# integrator_4pole.net
KiCad netlist of a schematic drawn in Altium Designer
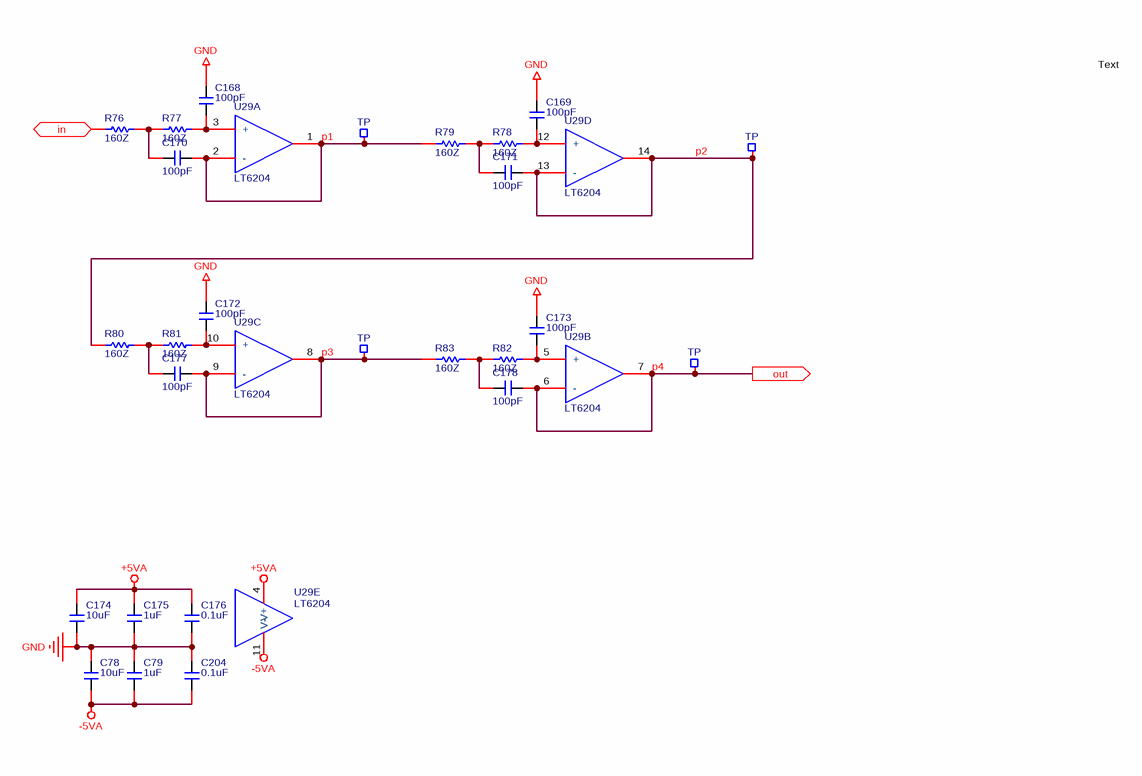
[diagram p0: integrator_4pole.SchDoc]

(export (version "E")
  (design (tool "Eeschema 10.0.6"))
  (components
    (comp (ref "C78")
      (value "10uF")
      (footprint "c1206")
      (description "CAP-CER, 2, 10uF, 10%, 35V, 1206")
      (fields
        (field (name "MANUFACTURER") "Taiyo Yuden")
        (field (name "MANUFACTURER PART NUMBER") "GMK316F106ZL-T")
      )
      (libsource (lib "stdlib") (part "CAP/GMK316F106ZL-T"))
    )
    (comp (ref "C79")
      (value "1uF")
      (footprint "C0603")
      (description "CAP-CER, 2, 1.0uF, 10%, 25V, 0603")
      (fields
        (field (name "MANUFACTURER") "Murata Electronics North America")
        (field (name "MANUFACTURER PART NUMBER") "GRM188R61E105KA12D")
      )
      (libsource (lib "stdlib") (part "Murata/GRM188R61E105KA12D"))
    )
    (comp (ref "C168")
      (value "100pF")
      (footprint "C0603")
      (description "CAP-CER, 0, 100pF, 10%, 50V, 0603")
      (fields
        (field (name "MANUFACTURER") "AVX Corporation")
        (field (name "MANUFACTURER PART NUMBER") "06035A101KAT2A")
      )
      (libsource (lib "stdlib") (part "AVX/06035A101KAT2A"))
    )
    (comp (ref "C169")
      (value "100pF")
      (footprint "C0603")
      (description "CAP-CER, 0, 100pF, 10%, 50V, 0603")
      (fields
        (field (name "MANUFACTURER") "AVX Corporation")
        (field (name "MANUFACTURER PART NUMBER") "06035A101KAT2A")
      )
      (libsource (lib "stdlib") (part "AVX/06035A101KAT2A"))
    )
    (comp (ref "C170")
      (value "100pF")
      (footprint "C0603")
      (description "CAP-CER, 0, 100pF, 10%, 50V, 0603")
      (fields
        (field (name "MANUFACTURER") "AVX Corporation")
        (field (name "MANUFACTURER PART NUMBER") "06035A101KAT2A")
      )
      (libsource (lib "stdlib") (part "AVX/06035A101KAT2A"))
    )
    (comp (ref "C171")
      (value "100pF")
      (footprint "C0603")
      (description "CAP-CER, 0, 100pF, 10%, 50V, 0603")
      (fields
        (field (name "MANUFACTURER") "AVX Corporation")
        (field (name "MANUFACTURER PART NUMBER") "06035A101KAT2A")
      )
      (libsource (lib "stdlib") (part "AVX/06035A101KAT2A"))
    )
    (comp (ref "C172")
      (value "100pF")
      (footprint "C0603")
      (description "CAP-CER, 0, 100pF, 10%, 50V, 0603")
      (fields
        (field (name "MANUFACTURER") "AVX Corporation")
        (field (name "MANUFACTURER PART NUMBER") "06035A101KAT2A")
      )
      (libsource (lib "stdlib") (part "AVX/06035A101KAT2A"))
    )
    (comp (ref "C173")
      (value "100pF")
      (footprint "C0603")
      (description "CAP-CER, 0, 100pF, 10%, 50V, 0603")
      (fields
        (field (name "MANUFACTURER") "AVX Corporation")
        (field (name "MANUFACTURER PART NUMBER") "06035A101KAT2A")
      )
      (libsource (lib "stdlib") (part "AVX/06035A101KAT2A"))
    )
    (comp (ref "C174")
      (value "10uF")
      (footprint "c1206")
      (description "CAP-CER, 2, 10uF, 10%, 35V, 1206")
      (fields
        (field (name "MANUFACTURER") "Taiyo Yuden")
        (field (name "MANUFACTURER PART NUMBER") "GMK316F106ZL-T")
      )
      (libsource (lib "stdlib") (part "CAP/GMK316F106ZL-T"))
    )
    (comp (ref "C175")
      (value "1uF")
      (footprint "C0603")
      (description "CAP-CER, 2, 1.0uF, 10%, 25V, 0603")
      (fields
        (field (name "MANUFACTURER") "Murata Electronics North America")
        (field (name "MANUFACTURER PART NUMBER") "GRM188R61E105KA12D")
      )
      (libsource (lib "stdlib") (part "Murata/GRM188R61E105KA12D"))
    )
    (comp (ref "C176")
      (value "0.1uF")
      (footprint "C0603")
      (description "CAP-CER, 2, 0.1uF, 10%, 50V, 0603, X7R")
      (fields
        (field (name "MANUFACTURER") "AVX Corporation")
        (field (name "MANUFACTURER PART NUMBER") "06035C104KAT2A")
      )
      (libsource (lib "stdlib") (part "CAP/06035C104KAT2A"))
    )
    (comp (ref "C177")
      (value "100pF")
      (footprint "C0603")
      (description "CAP-CER, 0, 100pF, 10%, 50V, 0603")
      (fields
        (field (name "MANUFACTURER") "AVX Corporation")
        (field (name "MANUFACTURER PART NUMBER") "06035A101KAT2A")
      )
      (libsource (lib "stdlib") (part "AVX/06035A101KAT2A"))
    )
    (comp (ref "C178")
      (value "100pF")
      (footprint "C0603")
      (description "CAP-CER, 0, 100pF, 10%, 50V, 0603")
      (fields
        (field (name "MANUFACTURER") "AVX Corporation")
        (field (name "MANUFACTURER PART NUMBER") "06035A101KAT2A")
      )
      (libsource (lib "stdlib") (part "AVX/06035A101KAT2A"))
    )
    (comp (ref "C204")
      (value "0.1uF")
      (footprint "C0603")
      (description "CAP-CER, 2, 0.1uF, 10%, 50V, 0603, X7R")
      (fields
        (field (name "MANUFACTURER") "AVX Corporation")
        (field (name "MANUFACTURER PART NUMBER") "06035C104KAT2A")
      )
      (libsource (lib "stdlib") (part "CAP/06035C104KAT2A"))
    )
    (comp (ref "R76")
      (value "160Z")
      (footprint "R0603")
      (description "RES0, SMD,  160Z, 1.0%, 1/10W, 0603")
      (fields
        (field (name "MANUFACTURER") "Vishay Dale")
        (field (name "MANUFACTURER PART NUMBER") "CRCW0603160RFKEA")
      )
      (libsource (lib "stdlib") (part "CRCW0603160RFKEA"))
    )
    (comp (ref "R77")
      (value "160Z")
      (footprint "R0603")
      (description "RES0, SMD,  160Z, 1.0%, 1/10W, 0603")
      (fields
        (field (name "MANUFACTURER") "Vishay Dale")
        (field (name "MANUFACTURER PART NUMBER") "CRCW0603160RFKEA")
      )
      (libsource (lib "stdlib") (part "CRCW0603160RFKEA"))
    )
    (comp (ref "R78")
      (value "160Z")
      (footprint "R0603")
      (description "RES0, SMD,  160Z, 1.0%, 1/10W, 0603")
      (fields
        (field (name "MANUFACTURER") "Vishay Dale")
        (field (name "MANUFACTURER PART NUMBER") "CRCW0603160RFKEA")
      )
      (libsource (lib "stdlib") (part "CRCW0603160RFKEA"))
    )
    (comp (ref "R79")
      (value "160Z")
      (footprint "R0603")
      (description "RES0, SMD,  160Z, 1.0%, 1/10W, 0603")
      (fields
        (field (name "MANUFACTURER") "Vishay Dale")
        (field (name "MANUFACTURER PART NUMBER") "CRCW0603160RFKEA")
      )
      (libsource (lib "stdlib") (part "CRCW0603160RFKEA"))
    )
    (comp (ref "R80")
      (value "160Z")
      (footprint "R0603")
      (description "RES0, SMD,  160Z, 1.0%, 1/10W, 0603")
      (fields
        (field (name "MANUFACTURER") "Vishay Dale")
        (field (name "MANUFACTURER PART NUMBER") "CRCW0603160RFKEA")
      )
      (libsource (lib "stdlib") (part "CRCW0603160RFKEA"))
    )
    (comp (ref "R81")
      (value "160Z")
      (footprint "R0603")
      (description "RES0, SMD,  160Z, 1.0%, 1/10W, 0603")
      (fields
        (field (name "MANUFACTURER") "Vishay Dale")
        (field (name "MANUFACTURER PART NUMBER") "CRCW0603160RFKEA")
      )
      (libsource (lib "stdlib") (part "CRCW0603160RFKEA"))
    )
    (comp (ref "R82")
      (value "160Z")
      (footprint "R0603")
      (description "RES0, SMD,  160Z, 1.0%, 1/10W, 0603")
      (fields
        (field (name "MANUFACTURER") "Vishay Dale")
        (field (name "MANUFACTURER PART NUMBER") "CRCW0603160RFKEA")
      )
      (libsource (lib "stdlib") (part "CRCW0603160RFKEA"))
    )
    (comp (ref "R83")
      (value "160Z")
      (footprint "R0603")
      (description "RES0, SMD,  160Z, 1.0%, 1/10W, 0603")
      (fields
        (field (name "MANUFACTURER") "Vishay Dale")
        (field (name "MANUFACTURER PART NUMBER") "CRCW0603160RFKEA")
      )
      (libsource (lib "stdlib") (part "CRCW0603160RFKEA"))
    )
    (comp (ref "TP8")
      (value "TP")
      (footprint "TP_MICRO")
      (description "Test Point, Round, Small")
      (libsource (lib "stdlib") (part "TP_MICRO"))
    )
    (comp (ref "TP33")
      (value "TP")
      (footprint "TP_MICRO")
      (description "Test Point, Round, Small")
      (libsource (lib "stdlib") (part "TP_MICRO"))
    )
    (comp (ref "TP34")
      (value "TP")
      (footprint "TP_MICRO")
      (description "Test Point, Round, Small")
      (libsource (lib "stdlib") (part "TP_MICRO"))
    )
    (comp (ref "TP35")
      (value "TP")
      (footprint "TP_MICRO")
      (description "Test Point, Round, Small")
      (libsource (lib "stdlib") (part "TP_MICRO"))
    )
    (comp (ref "U29")
      (value "LT6204")
      (footprint "SOIC-14")
      (description "OPA, 100MHz, Quad, RRIO, Unity Stable")
      (libsource (lib "stdlib") (part "LT6204 SOIC-14"))
    )
  )
  (nets
    (net (code "1") (name "+5VA") (class "Default")
      (node (ref "C174") (pin "1") (pinfunction "5_1") (pintype "passive"))
      (node (ref "C175") (pin "2") (pinfunction "2_2") (pintype "passive"))
      (node (ref "C176") (pin "2") (pinfunction "2_2") (pintype "passive"))
      (node (ref "U29") (pin "4") (pinfunction "V+_4") (pintype "passive"))
    )
    (net (code "2") (name "-5VA") (class "Default")
      (node (ref "C204") (pin "1") (pinfunction "5_1") (pintype "passive"))
      (node (ref "C78") (pin "2") (pinfunction "2_2") (pintype "passive"))
      (node (ref "C79") (pin "1") (pinfunction "5_1") (pintype "passive"))
      (node (ref "U29") (pin "11") (pinfunction "V-_11") (pintype "passive"))
    )
    (net (code "3") (name "/in") (class "Default")
      (node (ref "R76") (pin "1") (pinfunction "1_1") (pintype "passive"))
    )
    (net (code "4") (name "/p1") (class "Default")
      (node (ref "C170") (pin "2") (pinfunction "2_2") (pintype "passive"))
      (node (ref "R79") (pin "1") (pinfunction "1_1") (pintype "passive"))
      (node (ref "TP8") (pin "1") (pinfunction "1_1") (pintype "passive"))
      (node (ref "U29") (pin "1") (pinfunction "OUT_1") (pintype "passive"))
      (node (ref "U29") (pin "2") (pinfunction "-_2") (pintype "passive"))
    )
    (net (code "5") (name "/p2") (class "Default")
      (node (ref "C171") (pin "2") (pinfunction "2_2") (pintype "passive"))
      (node (ref "R80") (pin "1") (pinfunction "1_1") (pintype "passive"))
      (node (ref "TP33") (pin "1") (pinfunction "1_1") (pintype "passive"))
      (node (ref "U29") (pin "13") (pinfunction "-_13") (pintype "passive"))
      (node (ref "U29") (pin "14") (pinfunction "OUT_14") (pintype "passive"))
    )
    (net (code "6") (name "/p3") (class "Default")
      (node (ref "C177") (pin "2") (pinfunction "2_2") (pintype "passive"))
      (node (ref "R83") (pin "1") (pinfunction "1_1") (pintype "passive"))
      (node (ref "TP34") (pin "1") (pinfunction "1_1") (pintype "passive"))
      (node (ref "U29") (pin "8") (pinfunction "OUT_8") (pintype "passive"))
      (node (ref "U29") (pin "9") (pinfunction "-_9") (pintype "passive"))
    )
    (net (code "7") (name "/p4") (class "Default")
      (node (ref "C178") (pin "2") (pinfunction "2_2") (pintype "passive"))
      (node (ref "TP35") (pin "1") (pinfunction "1_1") (pintype "passive"))
      (node (ref "U29") (pin "6") (pinfunction "-_6") (pintype "passive"))
      (node (ref "U29") (pin "7") (pinfunction "OUT_7") (pintype "passive"))
    )
    (net (code "8") (name "GND") (class "Default")
      (node (ref "C168") (pin "2") (pinfunction "2_2") (pintype "passive"))
      (node (ref "C169") (pin "2") (pinfunction "2_2") (pintype "passive"))
      (node (ref "C172") (pin "2") (pinfunction "2_2") (pintype "passive"))
      (node (ref "C173") (pin "2") (pinfunction "2_2") (pintype "passive"))
      (node (ref "C174") (pin "2") (pinfunction "2_2") (pintype "passive"))
      (node (ref "C175") (pin "1") (pinfunction "5_1") (pintype "passive"))
      (node (ref "C176") (pin "1") (pinfunction "5_1") (pintype "passive"))
      (node (ref "C204") (pin "2") (pinfunction "2_2") (pintype "passive"))
      (node (ref "C78") (pin "1") (pinfunction "5_1") (pintype "passive"))
      (node (ref "C79") (pin "2") (pinfunction "2_2") (pintype "passive"))
    )
    (net (code "9") (name "Net-(C168-5)") (class "Default")
      (node (ref "C168") (pin "1") (pinfunction "5_1") (pintype "passive"))
      (node (ref "R77") (pin "2") (pinfunction "2_2") (pintype "passive"))
      (node (ref "U29") (pin "3") (pinfunction "+_3") (pintype "passive"))
    )
    (net (code "10") (name "Net-(C169-5)") (class "Default")
      (node (ref "C169") (pin "1") (pinfunction "5_1") (pintype "passive"))
      (node (ref "R78") (pin "2") (pinfunction "2_2") (pintype "passive"))
      (node (ref "U29") (pin "12") (pinfunction "+_12") (pintype "passive"))
    )
    (net (code "11") (name "Net-(C170-5)") (class "Default")
      (node (ref "C170") (pin "1") (pinfunction "5_1") (pintype "passive"))
      (node (ref "R76") (pin "2") (pinfunction "2_2") (pintype "passive"))
      (node (ref "R77") (pin "1") (pinfunction "1_1") (pintype "passive"))
    )
    (net (code "12") (name "Net-(C171-5)") (class "Default")
      (node (ref "C171") (pin "1") (pinfunction "5_1") (pintype "passive"))
      (node (ref "R78") (pin "1") (pinfunction "1_1") (pintype "passive"))
      (node (ref "R79") (pin "2") (pinfunction "2_2") (pintype "passive"))
    )
    (net (code "13") (name "Net-(C172-5)") (class "Default")
      (node (ref "C172") (pin "1") (pinfunction "5_1") (pintype "passive"))
      (node (ref "R81") (pin "2") (pinfunction "2_2") (pintype "passive"))
      (node (ref "U29") (pin "10") (pinfunction "+_10") (pintype "passive"))
    )
    (net (code "14") (name "Net-(C173-5)") (class "Default")
      (node (ref "C173") (pin "1") (pinfunction "5_1") (pintype "passive"))
      (node (ref "R82") (pin "2") (pinfunction "2_2") (pintype "passive"))
      (node (ref "U29") (pin "5") (pinfunction "+_5") (pintype "passive"))
    )
    (net (code "15") (name "Net-(C177-5)") (class "Default")
      (node (ref "C177") (pin "1") (pinfunction "5_1") (pintype "passive"))
      (node (ref "R80") (pin "2") (pinfunction "2_2") (pintype "passive"))
      (node (ref "R81") (pin "1") (pinfunction "1_1") (pintype "passive"))
    )
    (net (code "16") (name "Net-(C178-5)") (class "Default")
      (node (ref "C178") (pin "1") (pinfunction "5_1") (pintype "passive"))
      (node (ref "R82") (pin "1") (pinfunction "1_1") (pintype "passive"))
      (node (ref "R83") (pin "2") (pinfunction "2_2") (pintype "passive"))
    )
  )
)
